# segment1.net
KiCad netlist of a schematic drawn in Altium Designer
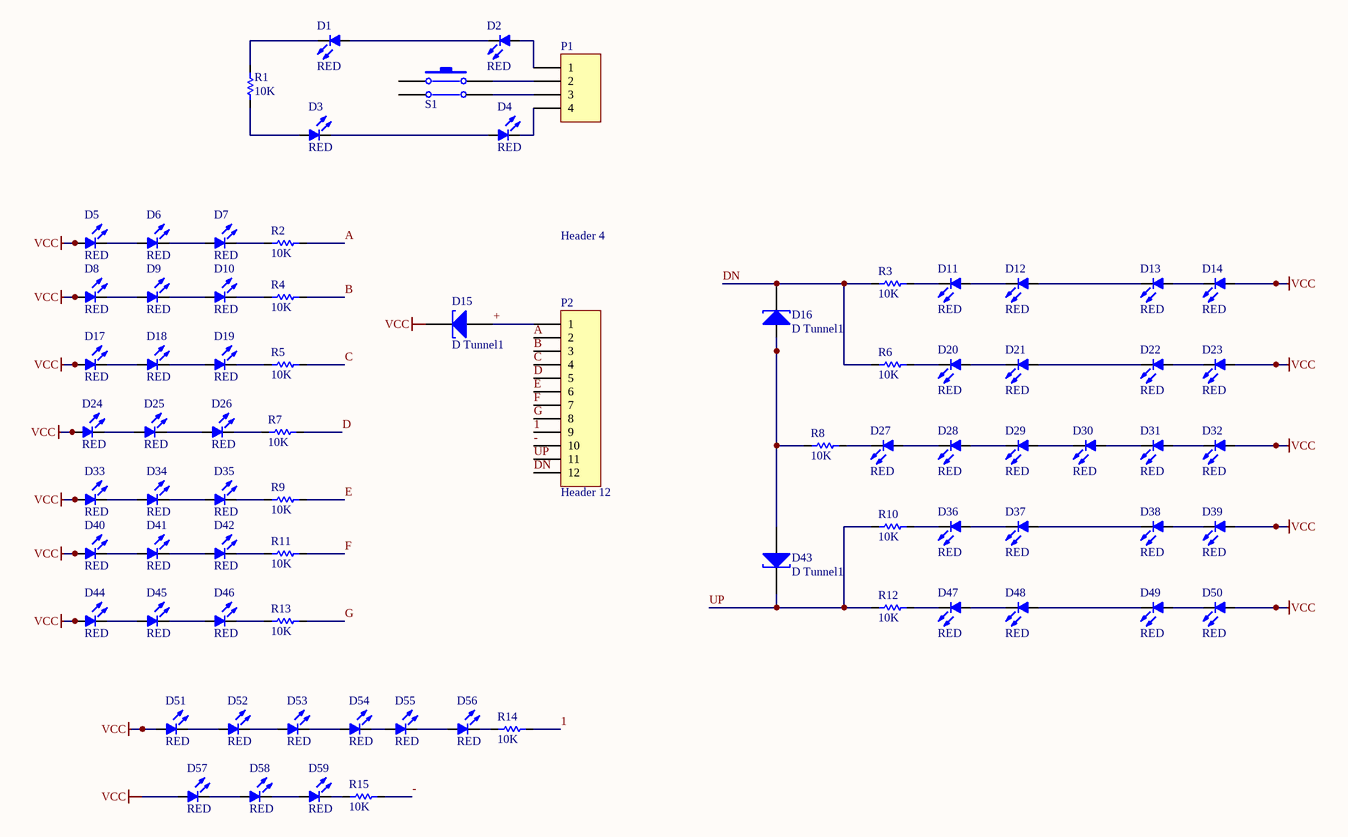
[diagram p0: segment1.SchDoc]

(export (version "E")
  (design (tool "Eeschema 10.0.6"))
  (components
    (comp (ref "D1")
      (value "MODEL")
      (footprint "RES 0805 (2012X06L)")
      (description "Typical LED")
      (fields (field (name "COLOR") "RED"))
      (libsource (lib "AltiumLib1") (part "LED 5mm"))
    )
    (comp (ref "D2")
      (value "MODEL")
      (footprint "RES 0805 (2012X06L)")
      (description "Typical LED")
      (fields (field (name "COLOR") "RED"))
      (libsource (lib "AltiumLib1") (part "LED 5mm"))
    )
    (comp (ref "D3")
      (value "MODEL")
      (footprint "RES 0805 (2012X06L)")
      (description "Typical LED")
      (fields (field (name "COLOR") "RED"))
      (libsource (lib "AltiumLib1") (part "LED 5mm"))
    )
    (comp (ref "D4")
      (value "MODEL")
      (footprint "RES 0805 (2012X06L)")
      (description "Typical LED")
      (fields (field (name "COLOR") "RED"))
      (libsource (lib "AltiumLib1") (part "LED 5mm"))
    )
    (comp (ref "D5")
      (value "MODEL")
      (footprint "RES 0805 (2012X06L)")
      (description "Typical LED")
      (fields (field (name "COLOR") "RED"))
      (libsource (lib "AltiumLib1") (part "LED 5mm"))
    )
    (comp (ref "D6")
      (value "MODEL")
      (footprint "RES 0805 (2012X06L)")
      (description "Typical LED")
      (fields (field (name "COLOR") "RED"))
      (libsource (lib "AltiumLib1") (part "LED 5mm"))
    )
    (comp (ref "D7")
      (value "MODEL")
      (footprint "RES 0805 (2012X06L)")
      (description "Typical LED")
      (fields (field (name "COLOR") "RED"))
      (libsource (lib "AltiumLib1") (part "LED 5mm"))
    )
    (comp (ref "D8")
      (value "MODEL")
      (footprint "RES 0805 (2012X06L)")
      (description "Typical LED")
      (fields (field (name "COLOR") "RED"))
      (libsource (lib "AltiumLib1") (part "LED 5mm"))
    )
    (comp (ref "D9")
      (value "MODEL")
      (footprint "RES 0805 (2012X06L)")
      (description "Typical LED")
      (fields (field (name "COLOR") "RED"))
      (libsource (lib "AltiumLib1") (part "LED 5mm"))
    )
    (comp (ref "D10")
      (value "MODEL")
      (footprint "RES 0805 (2012X06L)")
      (description "Typical LED")
      (fields (field (name "COLOR") "RED"))
      (libsource (lib "AltiumLib1") (part "LED 5mm"))
    )
    (comp (ref "D11")
      (value "MODEL")
      (footprint "RES 0805 (2012X06L)")
      (description "Typical LED")
      (fields (field (name "COLOR") "RED"))
      (libsource (lib "AltiumLib1") (part "LED 5mm"))
    )
    (comp (ref "D12")
      (value "MODEL")
      (footprint "RES 0805 (2012X06L)")
      (description "Typical LED")
      (fields (field (name "COLOR") "RED"))
      (libsource (lib "AltiumLib1") (part "LED 5mm"))
    )
    (comp (ref "D13")
      (value "MODEL")
      (footprint "RES 0805 (2012X06L)")
      (description "Typical LED")
      (fields (field (name "COLOR") "RED"))
      (libsource (lib "AltiumLib1") (part "LED 5mm"))
    )
    (comp (ref "D14")
      (value "MODEL")
      (footprint "RES 0805 (2012X06L)")
      (description "Typical LED")
      (fields (field (name "COLOR") "RED"))
      (libsource (lib "AltiumLib1") (part "LED 5mm"))
    )
    (comp (ref "D15")
      (value "D Tunnel1")
      (footprint "3.2X1.6X1.1")
      (description "Tunnel Diode - RLC Model")
      (fields (field (name "PUBLISHER") "Altium Limited"))
      (libsource (lib "Miscellaneous Devices") (part "D Tunnel1"))
    )
    (comp (ref "D16")
      (value "D Tunnel1")
      (footprint "3.2X1.6X1.1")
      (description "Tunnel Diode - RLC Model")
      (fields (field (name "PUBLISHER") "Altium Limited"))
      (libsource (lib "Miscellaneous Devices") (part "D Tunnel1"))
    )
    (comp (ref "D17")
      (value "MODEL")
      (footprint "RES 0805 (2012X06L)")
      (description "Typical LED")
      (fields (field (name "COLOR") "RED"))
      (libsource (lib "AltiumLib1") (part "LED 5mm"))
    )
    (comp (ref "D18")
      (value "MODEL")
      (footprint "RES 0805 (2012X06L)")
      (description "Typical LED")
      (fields (field (name "COLOR") "RED"))
      (libsource (lib "AltiumLib1") (part "LED 5mm"))
    )
    (comp (ref "D19")
      (value "MODEL")
      (footprint "RES 0805 (2012X06L)")
      (description "Typical LED")
      (fields (field (name "COLOR") "RED"))
      (libsource (lib "AltiumLib1") (part "LED 5mm"))
    )
    (comp (ref "D20")
      (value "MODEL")
      (footprint "RES 0805 (2012X06L)")
      (description "Typical LED")
      (fields (field (name "COLOR") "RED"))
      (libsource (lib "AltiumLib1") (part "LED 5mm"))
    )
    (comp (ref "D21")
      (value "MODEL")
      (footprint "RES 0805 (2012X06L)")
      (description "Typical LED")
      (fields (field (name "COLOR") "RED"))
      (libsource (lib "AltiumLib1") (part "LED 5mm"))
    )
    (comp (ref "D22")
      (value "MODEL")
      (footprint "RES 0805 (2012X06L)")
      (description "Typical LED")
      (fields (field (name "COLOR") "RED"))
      (libsource (lib "AltiumLib1") (part "LED 5mm"))
    )
    (comp (ref "D23")
      (value "MODEL")
      (footprint "RES 0805 (2012X06L)")
      (description "Typical LED")
      (fields (field (name "COLOR") "RED"))
      (libsource (lib "AltiumLib1") (part "LED 5mm"))
    )
    (comp (ref "D24")
      (value "MODEL")
      (footprint "RES 0805 (2012X06L)")
      (description "Typical LED")
      (fields (field (name "COLOR") "RED"))
      (libsource (lib "AltiumLib1") (part "LED 5mm"))
    )
    (comp (ref "D25")
      (value "MODEL")
      (footprint "RES 0805 (2012X06L)")
      (description "Typical LED")
      (fields (field (name "COLOR") "RED"))
      (libsource (lib "AltiumLib1") (part "LED 5mm"))
    )
    (comp (ref "D26")
      (value "MODEL")
      (footprint "RES 0805 (2012X06L)")
      (description "Typical LED")
      (fields (field (name "COLOR") "RED"))
      (libsource (lib "AltiumLib1") (part "LED 5mm"))
    )
    (comp (ref "D27")
      (value "MODEL")
      (footprint "RES 0805 (2012X06L)")
      (description "Typical LED")
      (fields (field (name "COLOR") "RED"))
      (libsource (lib "AltiumLib1") (part "LED 5mm"))
    )
    (comp (ref "D28")
      (value "MODEL")
      (footprint "RES 0805 (2012X06L)")
      (description "Typical LED")
      (fields (field (name "COLOR") "RED"))
      (libsource (lib "AltiumLib1") (part "LED 5mm"))
    )
    (comp (ref "D29")
      (value "MODEL")
      (footprint "RES 0805 (2012X06L)")
      (description "Typical LED")
      (fields (field (name "COLOR") "RED"))
      (libsource (lib "AltiumLib1") (part "LED 5mm"))
    )
    (comp (ref "D30")
      (value "MODEL")
      (footprint "RES 0805 (2012X06L)")
      (description "Typical LED")
      (fields (field (name "COLOR") "RED"))
      (libsource (lib "AltiumLib1") (part "LED 5mm"))
    )
    (comp (ref "D31")
      (value "MODEL")
      (footprint "RES 0805 (2012X06L)")
      (description "Typical LED")
      (fields (field (name "COLOR") "RED"))
      (libsource (lib "AltiumLib1") (part "LED 5mm"))
    )
    (comp (ref "D32")
      (value "MODEL")
      (footprint "RES 0805 (2012X06L)")
      (description "Typical LED")
      (fields (field (name "COLOR") "RED"))
      (libsource (lib "AltiumLib1") (part "LED 5mm"))
    )
    (comp (ref "D33")
      (value "MODEL")
      (footprint "RES 0805 (2012X06L)")
      (description "Typical LED")
      (fields (field (name "COLOR") "RED"))
      (libsource (lib "AltiumLib1") (part "LED 5mm"))
    )
    (comp (ref "D34")
      (value "MODEL")
      (footprint "RES 0805 (2012X06L)")
      (description "Typical LED")
      (fields (field (name "COLOR") "RED"))
      (libsource (lib "AltiumLib1") (part "LED 5mm"))
    )
    (comp (ref "D35")
      (value "MODEL")
      (footprint "RES 0805 (2012X06L)")
      (description "Typical LED")
      (fields (field (name "COLOR") "RED"))
      (libsource (lib "AltiumLib1") (part "LED 5mm"))
    )
    (comp (ref "D36")
      (value "MODEL")
      (footprint "RES 0805 (2012X06L)")
      (description "Typical LED")
      (fields (field (name "COLOR") "RED"))
      (libsource (lib "AltiumLib1") (part "LED 5mm"))
    )
    (comp (ref "D37")
      (value "MODEL")
      (footprint "RES 0805 (2012X06L)")
      (description "Typical LED")
      (fields (field (name "COLOR") "RED"))
      (libsource (lib "AltiumLib1") (part "LED 5mm"))
    )
    (comp (ref "D38")
      (value "MODEL")
      (footprint "RES 0805 (2012X06L)")
      (description "Typical LED")
      (fields (field (name "COLOR") "RED"))
      (libsource (lib "AltiumLib1") (part "LED 5mm"))
    )
    (comp (ref "D39")
      (value "MODEL")
      (footprint "RES 0805 (2012X06L)")
      (description "Typical LED")
      (fields (field (name "COLOR") "RED"))
      (libsource (lib "AltiumLib1") (part "LED 5mm"))
    )
    (comp (ref "D40")
      (value "MODEL")
      (footprint "RES 0805 (2012X06L)")
      (description "Typical LED")
      (fields (field (name "COLOR") "RED"))
      (libsource (lib "AltiumLib1") (part "LED 5mm"))
    )
    (comp (ref "D41")
      (value "MODEL")
      (footprint "RES 0805 (2012X06L)")
      (description "Typical LED")
      (fields (field (name "COLOR") "RED"))
      (libsource (lib "AltiumLib1") (part "LED 5mm"))
    )
    (comp (ref "D42")
      (value "MODEL")
      (footprint "RES 0805 (2012X06L)")
      (description "Typical LED")
      (fields (field (name "COLOR") "RED"))
      (libsource (lib "AltiumLib1") (part "LED 5mm"))
    )
    (comp (ref "D43")
      (value "D Tunnel1")
      (footprint "3.2X1.6X1.1")
      (description "Tunnel Diode - RLC Model")
      (fields (field (name "PUBLISHER") "Altium Limited"))
      (libsource (lib "Miscellaneous Devices") (part "D Tunnel1"))
    )
    (comp (ref "D44")
      (value "MODEL")
      (footprint "RES 0805 (2012X06L)")
      (description "Typical LED")
      (fields (field (name "COLOR") "RED"))
      (libsource (lib "AltiumLib1") (part "LED 5mm"))
    )
    (comp (ref "D45")
      (value "MODEL")
      (footprint "RES 0805 (2012X06L)")
      (description "Typical LED")
      (fields (field (name "COLOR") "RED"))
      (libsource (lib "AltiumLib1") (part "LED 5mm"))
    )
    (comp (ref "D46")
      (value "MODEL")
      (footprint "RES 0805 (2012X06L)")
      (description "Typical LED")
      (fields (field (name "COLOR") "RED"))
      (libsource (lib "AltiumLib1") (part "LED 5mm"))
    )
    (comp (ref "D47")
      (value "MODEL")
      (footprint "RES 0805 (2012X06L)")
      (description "Typical LED")
      (fields (field (name "COLOR") "RED"))
      (libsource (lib "AltiumLib1") (part "LED 5mm"))
    )
    (comp (ref "D48")
      (value "MODEL")
      (footprint "RES 0805 (2012X06L)")
      (description "Typical LED")
      (fields (field (name "COLOR") "RED"))
      (libsource (lib "AltiumLib1") (part "LED 5mm"))
    )
    (comp (ref "D49")
      (value "MODEL")
      (footprint "RES 0805 (2012X06L)")
      (description "Typical LED")
      (fields (field (name "COLOR") "RED"))
      (libsource (lib "AltiumLib1") (part "LED 5mm"))
    )
    (comp (ref "D50")
      (value "MODEL")
      (footprint "RES 0805 (2012X06L)")
      (description "Typical LED")
      (fields (field (name "COLOR") "RED"))
      (libsource (lib "AltiumLib1") (part "LED 5mm"))
    )
    (comp (ref "D51")
      (value "MODEL")
      (footprint "RES 0805 (2012X06L)")
      (description "Typical LED")
      (fields (field (name "COLOR") "RED"))
      (libsource (lib "AltiumLib1") (part "LED 5mm"))
    )
    (comp (ref "D52")
      (value "MODEL")
      (footprint "RES 0805 (2012X06L)")
      (description "Typical LED")
      (fields (field (name "COLOR") "RED"))
      (libsource (lib "AltiumLib1") (part "LED 5mm"))
    )
    (comp (ref "D53")
      (value "MODEL")
      (footprint "RES 0805 (2012X06L)")
      (description "Typical LED")
      (fields (field (name "COLOR") "RED"))
      (libsource (lib "AltiumLib1") (part "LED 5mm"))
    )
    (comp (ref "D54")
      (value "MODEL")
      (footprint "RES 0805 (2012X06L)")
      (description "Typical LED")
      (fields (field (name "COLOR") "RED"))
      (libsource (lib "AltiumLib1") (part "LED 5mm"))
    )
    (comp (ref "D55")
      (value "MODEL")
      (footprint "RES 0805 (2012X06L)")
      (description "Typical LED")
      (fields (field (name "COLOR") "RED"))
      (libsource (lib "AltiumLib1") (part "LED 5mm"))
    )
    (comp (ref "D56")
      (value "MODEL")
      (footprint "RES 0805 (2012X06L)")
      (description "Typical LED")
      (fields (field (name "COLOR") "RED"))
      (libsource (lib "AltiumLib1") (part "LED 5mm"))
    )
    (comp (ref "D57")
      (value "MODEL")
      (footprint "RES 0805 (2012X06L)")
      (description "Typical LED")
      (fields (field (name "COLOR") "RED"))
      (libsource (lib "AltiumLib1") (part "LED 5mm"))
    )
    (comp (ref "D58")
      (value "MODEL")
      (footprint "RES 0805 (2012X06L)")
      (description "Typical LED")
      (fields (field (name "COLOR") "RED"))
      (libsource (lib "AltiumLib1") (part "LED 5mm"))
    )
    (comp (ref "D59")
      (value "MODEL")
      (footprint "RES 0805 (2012X06L)")
      (description "Typical LED")
      (fields (field (name "COLOR") "RED"))
      (libsource (lib "AltiumLib1") (part "LED 5mm"))
    )
    (comp (ref "P1")
      (value "Header 4")
      (footprint "HDR1X4")
      (description "Header, 4-Pin")
      (fields (field (name "PUBLISHER") "Altium Limited"))
      (libsource (lib "Miscellaneous Connectors") (part "Header 4"))
    )
    (comp (ref "P2")
      (value "Header 12")
      (footprint "HDR1X12")
      (description "Header, 12-Pin")
      (fields (field (name "PUBLISHER") "Altium Limited"))
      (libsource (lib "Miscellaneous Connectors") (part "Header 12"))
    )
    (comp (ref "R1")
      (value "10K")
      (footprint "RES 1206 (3216X08L)")
      (description "Resistor")
      (fields (field (name "TOLERANCE") "5%") (field (name "POWER") "1/4 W"))
      (libsource (lib "AltiumLib1") (part "Resistor"))
    )
    (comp (ref "R2")
      (value "10K")
      (footprint "RES 1206 (3216X08L)")
      (description "Resistor")
      (fields (field (name "TOLERANCE") "5%") (field (name "POWER") "1/4 W"))
      (libsource (lib "AltiumLib1") (part "Resistor"))
    )
    (comp (ref "R3")
      (value "10K")
      (footprint "RES 1206 (3216X08L)")
      (description "Resistor")
      (fields (field (name "TOLERANCE") "5%") (field (name "POWER") "1/4 W"))
      (libsource (lib "AltiumLib1") (part "Resistor"))
    )
    (comp (ref "R4")
      (value "10K")
      (footprint "RES 1206 (3216X08L)")
      (description "Resistor")
      (fields (field (name "TOLERANCE") "5%") (field (name "POWER") "1/4 W"))
      (libsource (lib "AltiumLib1") (part "Resistor"))
    )
    (comp (ref "R5")
      (value "10K")
      (footprint "RES 1206 (3216X08L)")
      (description "Resistor")
      (fields (field (name "TOLERANCE") "5%") (field (name "POWER") "1/4 W"))
      (libsource (lib "AltiumLib1") (part "Resistor"))
    )
    (comp (ref "R6")
      (value "10K")
      (footprint "RES 1206 (3216X08L)")
      (description "Resistor")
      (fields (field (name "TOLERANCE") "5%") (field (name "POWER") "1/4 W"))
      (libsource (lib "AltiumLib1") (part "Resistor"))
    )
    (comp (ref "R7")
      (value "10K")
      (footprint "RES 1206 (3216X08L)")
      (description "Resistor")
      (fields (field (name "TOLERANCE") "5%") (field (name "POWER") "1/4 W"))
      (libsource (lib "AltiumLib1") (part "Resistor"))
    )
    (comp (ref "R8")
      (value "10K")
      (footprint "RES 1206 (3216X08L)")
      (description "Resistor")
      (fields (field (name "TOLERANCE") "5%") (field (name "POWER") "1/4 W"))
      (libsource (lib "AltiumLib1") (part "Resistor"))
    )
    (comp (ref "R9")
      (value "10K")
      (footprint "RES 1206 (3216X08L)")
      (description "Resistor")
      (fields (field (name "TOLERANCE") "5%") (field (name "POWER") "1/4 W"))
      (libsource (lib "AltiumLib1") (part "Resistor"))
    )
    (comp (ref "R10")
      (value "10K")
      (footprint "RES 1206 (3216X08L)")
      (description "Resistor")
      (fields (field (name "TOLERANCE") "5%") (field (name "POWER") "1/4 W"))
      (libsource (lib "AltiumLib1") (part "Resistor"))
    )
    (comp (ref "R11")
      (value "10K")
      (footprint "RES 1206 (3216X08L)")
      (description "Resistor")
      (fields (field (name "TOLERANCE") "5%") (field (name "POWER") "1/4 W"))
      (libsource (lib "AltiumLib1") (part "Resistor"))
    )
    (comp (ref "R12")
      (value "10K")
      (footprint "RES 1206 (3216X08L)")
      (description "Resistor")
      (fields (field (name "TOLERANCE") "5%") (field (name "POWER") "1/4 W"))
      (libsource (lib "AltiumLib1") (part "Resistor"))
    )
    (comp (ref "R13")
      (value "10K")
      (footprint "RES 1206 (3216X08L)")
      (description "Resistor")
      (fields (field (name "TOLERANCE") "5%") (field (name "POWER") "1/4 W"))
      (libsource (lib "AltiumLib1") (part "Resistor"))
    )
    (comp (ref "R14")
      (value "10K")
      (footprint "RES 1206 (3216X08L)")
      (description "Resistor")
      (fields (field (name "TOLERANCE") "5%") (field (name "POWER") "1/4 W"))
      (libsource (lib "AltiumLib1") (part "Resistor"))
    )
    (comp (ref "R15")
      (value "10K")
      (footprint "RES 1206 (3216X08L)")
      (description "Resistor")
      (fields (field (name "TOLERANCE") "5%") (field (name "POWER") "1/4 W"))
      (libsource (lib "AltiumLib1") (part "Resistor"))
    )
    (comp (ref "S1")
      (value "PUSH BUTTON DOUBLE")
      (footprint "PUSH BUTTON")
      (description "Switch")
      (libsource (lib "AltiumLib1") (part "PUSH BUTTON DOUBLE"))
    )
  )
  (nets
    (net (code "1") (name "/+") (class "Default")
      (node (ref "D15") (pin "1") (pinfunction "A_1") (pintype "passive"))
      (node (ref "P2") (pin "1") (pinfunction "1_1") (pintype "passive"))
    )
    (net (code "2") (name "/-") (class "Default")
      (node (ref "P2") (pin "10") (pinfunction "10_10") (pintype "passive"))
      (node (ref "R15") (pin "1") (pinfunction "1_1") (pintype "passive"))
    )
    (net (code "3") (name "/1") (class "Default")
      (node (ref "P2") (pin "9") (pinfunction "9_9") (pintype "passive"))
      (node (ref "R14") (pin "1") (pinfunction "1_1") (pintype "passive"))
    )
    (net (code "4") (name "/A") (class "Default")
      (node (ref "P2") (pin "2") (pinfunction "2_2") (pintype "passive"))
      (node (ref "R2") (pin "1") (pinfunction "1_1") (pintype "passive"))
    )
    (net (code "5") (name "/B") (class "Default")
      (node (ref "P2") (pin "3") (pinfunction "3_3") (pintype "passive"))
      (node (ref "R4") (pin "1") (pinfunction "1_1") (pintype "passive"))
    )
    (net (code "6") (name "/C") (class "Default")
      (node (ref "P2") (pin "4") (pinfunction "4_4") (pintype "passive"))
      (node (ref "R5") (pin "1") (pinfunction "1_1") (pintype "passive"))
    )
    (net (code "7") (name "/D") (class "Default")
      (node (ref "P2") (pin "5") (pinfunction "5_5") (pintype "passive"))
      (node (ref "R7") (pin "1") (pinfunction "1_1") (pintype "passive"))
    )
    (net (code "8") (name "/DN") (class "Default")
      (node (ref "D16") (pin "2") (pinfunction "K_2") (pintype "passive"))
      (node (ref "P2") (pin "12") (pinfunction "12_12") (pintype "passive"))
      (node (ref "R3") (pin "1") (pinfunction "1_1") (pintype "passive"))
      (node (ref "R6") (pin "1") (pinfunction "1_1") (pintype "passive"))
    )
    (net (code "9") (name "/E") (class "Default")
      (node (ref "P2") (pin "6") (pinfunction "6_6") (pintype "passive"))
      (node (ref "R9") (pin "1") (pinfunction "1_1") (pintype "passive"))
    )
    (net (code "10") (name "/F") (class "Default")
      (node (ref "P2") (pin "7") (pinfunction "7_7") (pintype "passive"))
      (node (ref "R11") (pin "1") (pinfunction "1_1") (pintype "passive"))
    )
    (net (code "11") (name "/G") (class "Default")
      (node (ref "P2") (pin "8") (pinfunction "8_8") (pintype "passive"))
      (node (ref "R13") (pin "1") (pinfunction "1_1") (pintype "passive"))
    )
    (net (code "12") (name "/UP") (class "Default")
      (node (ref "D43") (pin "2") (pinfunction "K_2") (pintype "passive"))
      (node (ref "P2") (pin "11") (pinfunction "11_11") (pintype "passive"))
      (node (ref "R10") (pin "1") (pinfunction "1_1") (pintype "passive"))
      (node (ref "R12") (pin "1") (pinfunction "1_1") (pintype "passive"))
    )
    (net (code "13") (name "Net-(D1-A)") (class "Default")
      (node (ref "D1") (pin "1") (pinfunction "A_1") (pintype "passive"))
      (node (ref "D2") (pin "2") (pinfunction "K_2") (pintype "passive"))
    )
    (net (code "14") (name "Net-(D1-K)") (class "Default")
      (node (ref "D1") (pin "2") (pinfunction "K_2") (pintype "passive"))
      (node (ref "R1") (pin "2") (pinfunction "2_2") (pintype "passive"))
    )
    (net (code "15") (name "Net-(D2-A)") (class "Default")
      (node (ref "D2") (pin "1") (pinfunction "A_1") (pintype "passive"))
      (node (ref "P1") (pin "1") (pinfunction "1_1") (pintype "passive"))
    )
    (net (code "16") (name "Net-(D3-A)") (class "Default")
      (node (ref "D3") (pin "1") (pinfunction "A_1") (pintype "passive"))
      (node (ref "R1") (pin "1") (pinfunction "1_1") (pintype "passive"))
    )
    (net (code "17") (name "Net-(D3-K)") (class "Default")
      (node (ref "D3") (pin "2") (pinfunction "K_2") (pintype "passive"))
      (node (ref "D4") (pin "1") (pinfunction "A_1") (pintype "passive"))
    )
    (net (code "18") (name "Net-(D4-K)") (class "Default")
      (node (ref "D4") (pin "2") (pinfunction "K_2") (pintype "passive"))
      (node (ref "P1") (pin "4") (pinfunction "4_4") (pintype "passive"))
    )
    (net (code "19") (name "Net-(D5-K)") (class "Default")
      (node (ref "D5") (pin "2") (pinfunction "K_2") (pintype "passive"))
      (node (ref "D6") (pin "1") (pinfunction "A_1") (pintype "passive"))
    )
    (net (code "20") (name "Net-(D6-K)") (class "Default")
      (node (ref "D6") (pin "2") (pinfunction "K_2") (pintype "passive"))
      (node (ref "D7") (pin "1") (pinfunction "A_1") (pintype "passive"))
    )
    (net (code "21") (name "Net-(D7-K)") (class "Default")
      (node (ref "D7") (pin "2") (pinfunction "K_2") (pintype "passive"))
      (node (ref "R2") (pin "2") (pinfunction "2_2") (pintype "passive"))
    )
    (net (code "22") (name "Net-(D8-K)") (class "Default")
      (node (ref "D8") (pin "2") (pinfunction "K_2") (pintype "passive"))
      (node (ref "D9") (pin "1") (pinfunction "A_1") (pintype "passive"))
    )
    (net (code "23") (name "Net-(D10-A)") (class "Default")
      (node (ref "D10") (pin "1") (pinfunction "A_1") (pintype "passive"))
      (node (ref "D9") (pin "2") (pinfunction "K_2") (pintype "passive"))
    )
    (net (code "24") (name "Net-(D10-K)") (class "Default")
      (node (ref "D10") (pin "2") (pinfunction "K_2") (pintype "passive"))
      (node (ref "R4") (pin "2") (pinfunction "2_2") (pintype "passive"))
    )
    (net (code "25") (name "Net-(D11-A)") (class "Default")
      (node (ref "D11") (pin "1") (pinfunction "A_1") (pintype "passive"))
      (node (ref "D12") (pin "2") (pinfunction "K_2") (pintype "passive"))
    )
    (net (code "26") (name "Net-(D11-K)") (class "Default")
      (node (ref "D11") (pin "2") (pinfunction "K_2") (pintype "passive"))
      (node (ref "R3") (pin "2") (pinfunction "2_2") (pintype "passive"))
    )
    (net (code "27") (name "Net-(D12-A)") (class "Default")
      (node (ref "D12") (pin "1") (pinfunction "A_1") (pintype "passive"))
      (node (ref "D13") (pin "2") (pinfunction "K_2") (pintype "passive"))
    )
    (net (code "28") (name "Net-(D13-A)") (class "Default")
      (node (ref "D13") (pin "1") (pinfunction "A_1") (pintype "passive"))
      (node (ref "D14") (pin "2") (pinfunction "K_2") (pintype "passive"))
    )
    (net (code "29") (name "Net-(D16-A)") (class "Default")
      (node (ref "D16") (pin "1") (pinfunction "A_1") (pintype "passive"))
      (node (ref "D43") (pin "1") (pinfunction "A_1") (pintype "passive"))
      (node (ref "R8") (pin "1") (pinfunction "1_1") (pintype "passive"))
    )
    (net (code "30") (name "Net-(D17-K)") (class "Default")
      (node (ref "D17") (pin "2") (pinfunction "K_2") (pintype "passive"))
      (node (ref "D18") (pin "1") (pinfunction "A_1") (pintype "passive"))
    )
    (net (code "31") (name "Net-(D18-K)") (class "Default")
      (node (ref "D18") (pin "2") (pinfunction "K_2") (pintype "passive"))
      (node (ref "D19") (pin "1") (pinfunction "A_1") (pintype "passive"))
    )
    (net (code "32") (name "Net-(D19-K)") (class "Default")
      (node (ref "D19") (pin "2") (pinfunction "K_2") (pintype "passive"))
      (node (ref "R5") (pin "2") (pinfunction "2_2") (pintype "passive"))
    )
    (net (code "33") (name "Net-(D20-A)") (class "Default")
      (node (ref "D20") (pin "1") (pinfunction "A_1") (pintype "passive"))
      (node (ref "D21") (pin "2") (pinfunction "K_2") (pintype "passive"))
    )
    (net (code "34") (name "Net-(D20-K)") (class "Default")
      (node (ref "D20") (pin "2") (pinfunction "K_2") (pintype "passive"))
      (node (ref "R6") (pin "2") (pinfunction "2_2") (pintype "passive"))
    )
    (net (code "35") (name "Net-(D21-A)") (class "Default")
      (node (ref "D21") (pin "1") (pinfunction "A_1") (pintype "passive"))
      (node (ref "D22") (pin "2") (pinfunction "K_2") (pintype "passive"))
    )
    (net (code "36") (name "Net-(D22-A)") (class "Default")
      (node (ref "D22") (pin "1") (pinfunction "A_1") (pintype "passive"))
      (node (ref "D23") (pin "2") (pinfunction "K_2") (pintype "passive"))
    )
    (net (code "37") (name "Net-(D24-K)") (class "Default")
      (node (ref "D24") (pin "2") (pinfunction "K_2") (pintype "passive"))
      (node (ref "D25") (pin "1") (pinfunction "A_1") (pintype "passive"))
    )
    (net (code "38") (name "Net-(D25-K)") (class "Default")
      (node (ref "D25") (pin "2") (pinfunction "K_2") (pintype "passive"))
      (node (ref "D26") (pin "1") (pinfunction "A_1") (pintype "passive"))
    )
    (net (code "39") (name "Net-(D26-K)") (class "Default")
      (node (ref "D26") (pin "2") (pinfunction "K_2") (pintype "passive"))
      (node (ref "R7") (pin "2") (pinfunction "2_2") (pintype "passive"))
    )
    (net (code "40") (name "Net-(D27-A)") (class "Default")
      (node (ref "D27") (pin "1") (pinfunction "A_1") (pintype "passive"))
      (node (ref "D28") (pin "2") (pinfunction "K_2") (pintype "passive"))
    )
    (net (code "41") (name "Net-(D27-K)") (class "Default")
      (node (ref "D27") (pin "2") (pinfunction "K_2") (pintype "passive"))
      (node (ref "R8") (pin "2") (pinfunction "2_2") (pintype "passive"))
    )
    (net (code "42") (name "Net-(D28-A)") (class "Default")
      (node (ref "D28") (pin "1") (pinfunction "A_1") (pintype "passive"))
      (node (ref "D29") (pin "2") (pinfunction "K_2") (pintype "passive"))
    )
    (net (code "43") (name "Net-(D29-A)") (class "Default")
      (node (ref "D29") (pin "1") (pinfunction "A_1") (pintype "passive"))
      (node (ref "D30") (pin "2") (pinfunction "K_2") (pintype "passive"))
    )
    (net (code "44") (name "Net-(D30-A)") (class "Default")
      (node (ref "D30") (pin "1") (pinfunction "A_1") (pintype "passive"))
      (node (ref "D31") (pin "2") (pinfunction "K_2") (pintype "passive"))
    )
    (net (code "45") (name "Net-(D31-A)") (class "Default")
      (node (ref "D31") (pin "1") (pinfunction "A_1") (pintype "passive"))
      (node (ref "D32") (pin "2") (pinfunction "K_2") (pintype "passive"))
    )
    (net (code "46") (name "Net-(D33-K)") (class "Default")
      (node (ref "D33") (pin "2") (pinfunction "K_2") (pintype "passive"))
      (node (ref "D34") (pin "1") (pinfunction "A_1") (pintype "passive"))
    )
    (net (code "47") (name "Net-(D34-K)") (class "Default")
      (node (ref "D34") (pin "2") (pinfunction "K_2") (pintype "passive"))
      (node (ref "D35") (pin "1") (pinfunction "A_1") (pintype "passive"))
    )
    (net (code "48") (name "Net-(D35-K)") (class "Default")
      (node (ref "D35") (pin "2") (pinfunction "K_2") (pintype "passive"))
      (node (ref "R9") (pin "2") (pinfunction "2_2") (pintype "passive"))
    )
    (net (code "49") (name "Net-(D36-A)") (class "Default")
      (node (ref "D36") (pin "1") (pinfunction "A_1") (pintype "passive"))
      (node (ref "D37") (pin "2") (pinfunction "K_2") (pintype "passive"))
    )
    (net (code "50") (name "Net-(D36-K)") (class "Default")
      (node (ref "D36") (pin "2") (pinfunction "K_2") (pintype "passive"))
      (node (ref "R10") (pin "2") (pinfunction "2_2") (pintype "passive"))
    )
    (net (code "51") (name "Net-(D37-A)") (class "Default")
      (node (ref "D37") (pin "1") (pinfunction "A_1") (pintype "passive"))
      (node (ref "D38") (pin "2") (pinfunction "K_2") (pintype "passive"))
    )
    (net (code "52") (name "Net-(D38-A)") (class "Default")
      (node (ref "D38") (pin "1") (pinfunction "A_1") (pintype "passive"))
      (node (ref "D39") (pin "2") (pinfunction "K_2") (pintype "passive"))
    )
    (net (code "53") (name "Net-(D40-K)") (class "Default")
      (node (ref "D40") (pin "2") (pinfunction "K_2") (pintype "passive"))
      (node (ref "D41") (pin "1") (pinfunction "A_1") (pintype "passive"))
    )
    (net (code "54") (name "Net-(D41-K)") (class "Default")
      (node (ref "D41") (pin "2") (pinfunction "K_2") (pintype "passive"))
      (node (ref "D42") (pin "1") (pinfunction "A_1") (pintype "passive"))
    )
    (net (code "55") (name "Net-(D42-K)") (class "Default")
      (node (ref "D42") (pin "2") (pinfunction "K_2") (pintype "passive"))
      (node (ref "R11") (pin "2") (pinfunction "2_2") (pintype "passive"))
    )
    (net (code "56") (name "Net-(D44-K)") (class "Default")
      (node (ref "D44") (pin "2") (pinfunction "K_2") (pintype "passive"))
      (node (ref "D45") (pin "1") (pinfunction "A_1") (pintype "passive"))
    )
    (net (code "57") (name "Net-(D45-K)") (class "Default")
      (node (ref "D45") (pin "2") (pinfunction "K_2") (pintype "passive"))
      (node (ref "D46") (pin "1") (pinfunction "A_1") (pintype "passive"))
    )
    (net (code "58") (name "Net-(D46-K)") (class "Default")
      (node (ref "D46") (pin "2") (pinfunction "K_2") (pintype "passive"))
      (node (ref "R13") (pin "2") (pinfunction "2_2") (pintype "passive"))
    )
    (net (code "59") (name "Net-(D47-A)") (class "Default")
      (node (ref "D47") (pin "1") (pinfunction "A_1") (pintype "passive"))
      (node (ref "D48") (pin "2") (pinfunction "K_2") (pintype "passive"))
    )
    (net (code "60") (name "Net-(D47-K)") (class "Default")
      (node (ref "D47") (pin "2") (pinfunction "K_2") (pintype "passive"))
      (node (ref "R12") (pin "2") (pinfunction "2_2") (pintype "passive"))
    )
    (net (code "61") (name "Net-(D48-A)") (class "Default")
      (node (ref "D48") (pin "1") (pinfunction "A_1") (pintype "passive"))
      (node (ref "D49") (pin "2") (pinfunction "K_2") (pintype "passive"))
    )
    (net (code "62") (name "Net-(D49-A)") (class "Default")
      (node (ref "D49") (pin "1") (pinfunction "A_1") (pintype "passive"))
      (node (ref "D50") (pin "2") (pinfunction "K_2") (pintype "passive"))
    )
    (net (code "63") (name "Net-(D51-K)") (class "Default")
      (node (ref "D51") (pin "2") (pinfunction "K_2") (pintype "passive"))
      (node (ref "D52") (pin "1") (pinfunction "A_1") (pintype "passive"))
    )
    (net (code "64") (name "Net-(D52-K)") (class "Default")
      (node (ref "D52") (pin "2") (pinfunction "K_2") (pintype "passive"))
      (node (ref "D53") (pin "1") (pinfunction "A_1") (pintype "passive"))
    )
    (net (code "65") (name "Net-(D53-K)") (class "Default")
      (node (ref "D53") (pin "2") (pinfunction "K_2") (pintype "passive"))
      (node (ref "D54") (pin "1") (pinfunction "A_1") (pintype "passive"))
    )
    (net (code "66") (name "Net-(D54-K)") (class "Default")
      (node (ref "D54") (pin "2") (pinfunction "K_2") (pintype "passive"))
      (node (ref "D55") (pin "1") (pinfunction "A_1") (pintype "passive"))
    )
    (net (code "67") (name "Net-(D55-K)") (class "Default")
      (node (ref "D55") (pin "2") (pinfunction "K_2") (pintype "passive"))
      (node (ref "D56") (pin "1") (pinfunction "A_1") (pintype "passive"))
    )
    (net (code "68") (name "Net-(D56-K)") (class "Default")
      (node (ref "D56") (pin "2") (pinfunction "K_2") (pintype "passive"))
      (node (ref "R14") (pin "2") (pinfunction "2_2") (pintype "passive"))
    )
    (net (code "69") (name "Net-(D57-K)") (class "Default")
      (node (ref "D57") (pin "2") (pinfunction "K_2") (pintype "passive"))
      (node (ref "D58") (pin "1") (pinfunction "A_1") (pintype "passive"))
    )
    (net (code "70") (name "Net-(D58-K)") (class "Default")
      (node (ref "D58") (pin "2") (pinfunction "K_2") (pintype "passive"))
      (node (ref "D59") (pin "1") (pinfunction "A_1") (pintype "passive"))
    )
    (net (code "71") (name "Net-(D59-K)") (class "Default")
      (node (ref "D59") (pin "2") (pinfunction "K_2") (pintype "passive"))
      (node (ref "R15") (pin "2") (pinfunction "2_2") (pintype "passive"))
    )
    (net (code "72") (name "Net-(P1-Pad2)") (class "Default")
      (node (ref "P1") (pin "2") (pinfunction "2_2") (pintype "passive"))
      (node (ref "S1") (pin "2") (pinfunction "2_2") (pintype "passive"))
    )
    (net (code "73") (name "Net-(P1-Pad3)") (class "Default")
      (node (ref "P1") (pin "3") (pinfunction "3_3") (pintype "passive"))
      (node (ref "S1") (pin "4") (pinfunction "4_4") (pintype "passive"))
    )
    (net (code "74") (name "VCC") (class "Default")
      (node (ref "D14") (pin "1") (pinfunction "A_1") (pintype "passive"))
      (node (ref "D15") (pin "2") (pinfunction "K_2") (pintype "passive"))
      (node (ref "D17") (pin "1") (pinfunction "A_1") (pintype "passive"))
      (node (ref "D23") (pin "1") (pinfunction "A_1") (pintype "passive"))
      (node (ref "D24") (pin "1") (pinfunction "A_1") (pintype "passive"))
      (node (ref "D32") (pin "1") (pinfunction "A_1") (pintype "passive"))
      (node (ref "D33") (pin "1") (pinfunction "A_1") (pintype "passive"))
      (node (ref "D39") (pin "1") (pinfunction "A_1") (pintype "passive"))
      (node (ref "D40") (pin "1") (pinfunction "A_1") (pintype "passive"))
      (node (ref "D44") (pin "1") (pinfunction "A_1") (pintype "passive"))
      (node (ref "D5") (pin "1") (pinfunction "A_1") (pintype "passive"))
      (node (ref "D50") (pin "1") (pinfunction "A_1") (pintype "passive"))
      (node (ref "D51") (pin "1") (pinfunction "A_1") (pintype "passive"))
      (node (ref "D57") (pin "1") (pinfunction "A_1") (pintype "passive"))
      (node (ref "D8") (pin "1") (pinfunction "A_1") (pintype "passive"))
    )
    (net (code "75") (name "unconnected-(S1-Pad1)") (class "Default")
      (node (ref "S1") (pin "1") (pinfunction "1_1") (pintype "passive"))
    )
    (net (code "76") (name "unconnected-(S1-Pad3)") (class "Default")
      (node (ref "S1") (pin "3") (pinfunction "3_3") (pintype "passive"))
    )
  )
)
